# remote_station.net
KiCad netlist of a schematic drawn in EAGLE
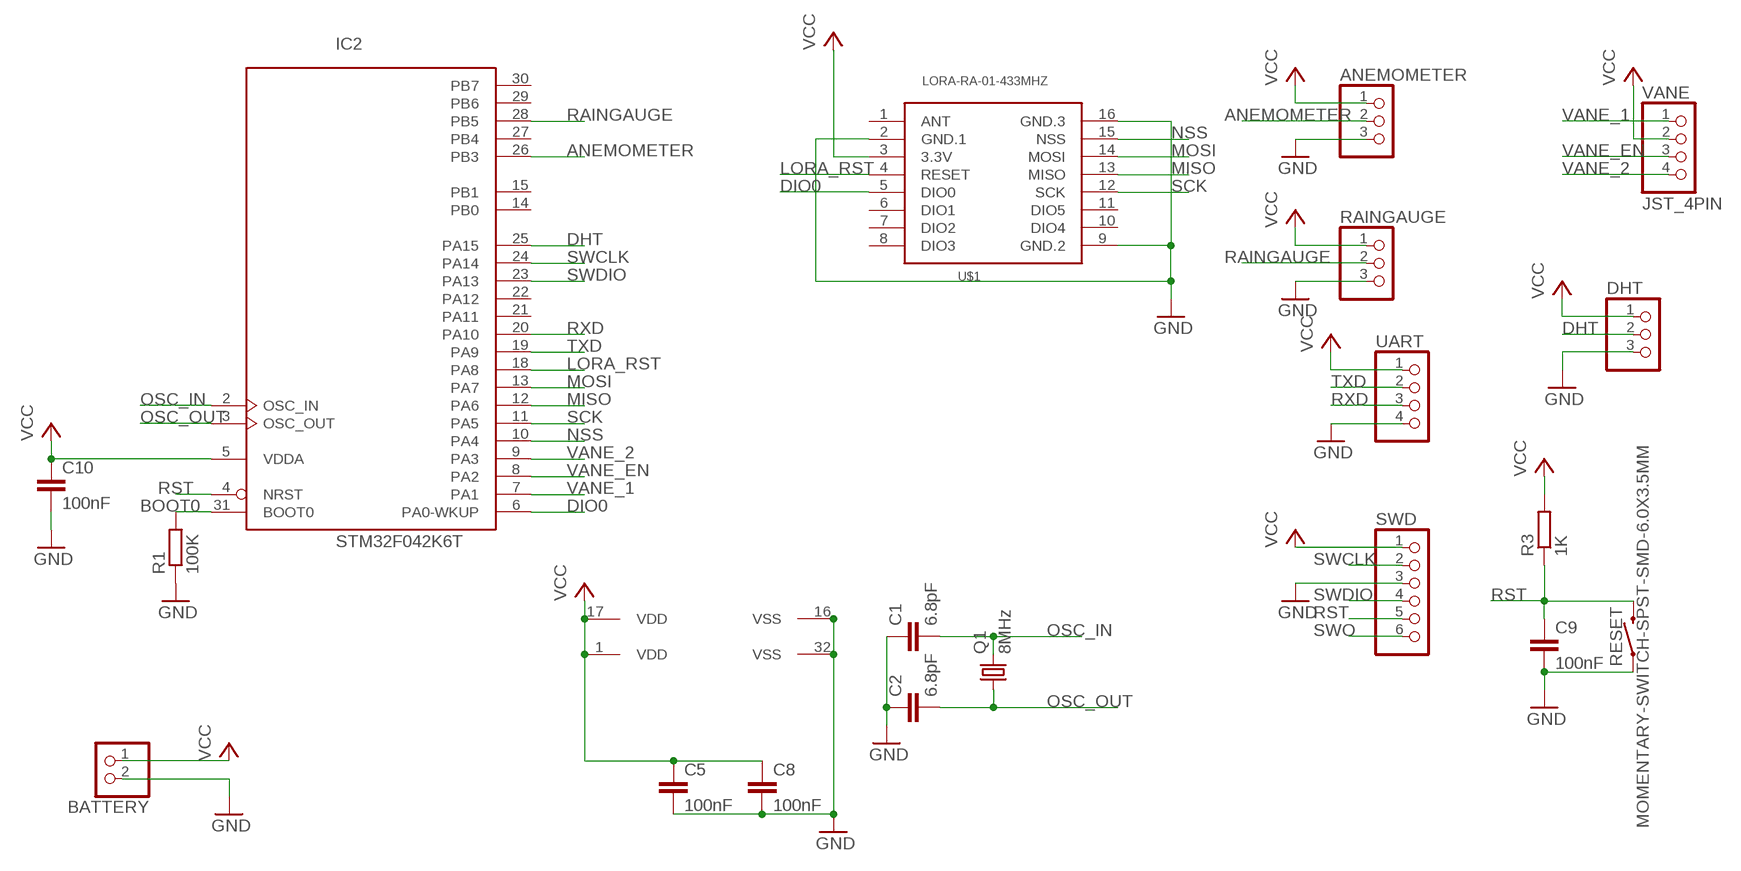
[diagram p0: schematic, sheet 1]

(export (version "E")
  (design (tool "Eeschema 10.0.6"))
  (components
    (comp (ref "ANEMOMETER")
      (value "JST_3PIN")
      (footprint "eagle-import:JSTPH3")
      (libsource (lib "eagle-import") (part "JST_3PIN"))
    )
    (comp (ref "BATTERY")
      (value "JST_2PIN-SMT-RA")
      (footprint "eagle-import:JST-PH-2-SMT-RA")
      (libsource (lib "eagle-import") (part "JST_2PIN-SMT-RA"))
    )
    (comp (ref "C1")
      (value "6.8pF")
      (footprint "eagle-import:C0805K")
      (libsource (lib "eagle-import") (part "C-EUC0805K"))
    )
    (comp (ref "C2")
      (value "6.8pF")
      (footprint "eagle-import:C0805K")
      (libsource (lib "eagle-import") (part "C-EUC0805K"))
    )
    (comp (ref "C5")
      (value "100nF")
      (footprint "eagle-import:C0805K")
      (libsource (lib "eagle-import") (part "C-EUC0805K"))
    )
    (comp (ref "C8")
      (value "100nF")
      (footprint "eagle-import:C0805K")
      (libsource (lib "eagle-import") (part "C-EUC0805K"))
    )
    (comp (ref "C9")
      (value "100nF")
      (footprint "eagle-import:C0805K")
      (libsource (lib "eagle-import") (part "C-EUC0805K"))
    )
    (comp (ref "C10")
      (value "100nF")
      (footprint "eagle-import:C0805K")
      (libsource (lib "eagle-import") (part "C-EUC0805K"))
    )
    (comp (ref "DHT")
      (value "JST_3PIN")
      (footprint "eagle-import:JSTPH3")
      (libsource (lib "eagle-import") (part "JST_3PIN"))
    )
    (comp (ref "IC2")
      (value "STM32F042K6T")
      (footprint "eagle-import:LQFP32")
      (libsource (lib "eagle-import") (part "STM32F042KT6"))
    )
    (comp (ref "Q1")
      (value "8MHz")
      (footprint "eagle-import:HC49UP")
      (libsource (lib "eagle-import") (part "CRYSTALHC49UP"))
    )
    (comp (ref "R1")
      (value "100K")
      (footprint "eagle-import:R0805W")
      (libsource (lib "eagle-import") (part "R-EU_R0805W"))
    )
    (comp (ref "R3")
      (value "1K")
      (footprint "eagle-import:R0805W")
      (libsource (lib "eagle-import") (part "R-EU_R0805W"))
    )
    (comp (ref "RAINGAUGE")
      (value "JST_3PIN")
      (footprint "eagle-import:JSTPH3")
      (libsource (lib "eagle-import") (part "JST_3PIN"))
    )
    (comp (ref "RESET")
      (value "MOMENTARY-SWITCH-SPST-SMD-6.0X3.5MM")
      (footprint "eagle-import:TACTILE_SWITCH_SMD_6.0X3.5MM")
      (libsource (lib "eagle-import") (part "MOMENTARY-SWITCH-SPST-SMD-6.0X3.5MM"))
    )
    (comp (ref "SWD")
      (value "PINHD-1X6")
      (footprint "eagle-import:1X06")
      (libsource (lib "eagle-import") (part "PINHD-1X6"))
    )
    (comp (ref "U$1")
      (value "LORA-RA-01-433MHZ")
      (footprint "eagle-import:LORA-RA1-SMD")
      (libsource (lib "eagle-import") (part "LORA-RA-01-433MHZ"))
    )
    (comp (ref "UART")
      (value "PINHD-1X4")
      (footprint "eagle-import:1X04")
      (libsource (lib "eagle-import") (part "PINHD-1X4"))
    )
    (comp (ref "VANE")
      (value "JST_4PIN")
      (footprint "eagle-import:JST-PH-2-SMT-RA")
      (libsource (lib "eagle-import") (part "JST_4PIN"))
    )
  )
  (nets
    (net (code "1") (name "/ANEMOMETER") (class "Default")
      (node (ref "ANEMOMETER") (pin "2") (pinfunction "2_2") (pintype "passive"))
      (node (ref "IC2") (pin "26") (pinfunction "PB3_26") (pintype "bidirectional"))
    )
    (net (code "2") (name "/BOOT0") (class "Default")
      (node (ref "IC2") (pin "31") (pinfunction "BOOT0_31") (pintype "input"))
      (node (ref "R1") (pin "2") (pinfunction "2_2") (pintype "passive"))
    )
    (net (code "3") (name "/DHT") (class "Default")
      (node (ref "DHT") (pin "2") (pinfunction "2_2") (pintype "passive"))
      (node (ref "IC2") (pin "25") (pinfunction "PA15_25") (pintype "bidirectional"))
    )
    (net (code "4") (name "/DIO0") (class "Default")
      (node (ref "IC2") (pin "6") (pinfunction "PA0-WKUP_6") (pintype "bidirectional"))
      (node (ref "U$1") (pin "5") (pinfunction "DIO0_5") (pintype "bidirectional"))
    )
    (net (code "5") (name "/LORA_RST") (class "Default")
      (node (ref "IC2") (pin "18") (pinfunction "PA8_18") (pintype "bidirectional"))
      (node (ref "U$1") (pin "4") (pinfunction "RESET_4") (pintype "bidirectional"))
    )
    (net (code "6") (name "/MISO") (class "Default")
      (node (ref "IC2") (pin "12") (pinfunction "PA6_12") (pintype "bidirectional"))
      (node (ref "U$1") (pin "13") (pinfunction "MISO_13") (pintype "bidirectional"))
    )
    (net (code "7") (name "/MOSI") (class "Default")
      (node (ref "IC2") (pin "13") (pinfunction "PA7_13") (pintype "bidirectional"))
      (node (ref "U$1") (pin "14") (pinfunction "MOSI_14") (pintype "bidirectional"))
    )
    (net (code "8") (name "/NSS") (class "Default")
      (node (ref "IC2") (pin "10") (pinfunction "PA4_10") (pintype "bidirectional"))
      (node (ref "U$1") (pin "15") (pinfunction "NSS_15") (pintype "bidirectional"))
    )
    (net (code "9") (name "/OSC_IN") (class "Default")
      (node (ref "C1") (pin "2") (pinfunction "2_2") (pintype "passive"))
      (node (ref "IC2") (pin "2") (pinfunction "OSC_IN_2") (pintype "bidirectional"))
      (node (ref "Q1") (pin "2") (pinfunction "2_2") (pintype "passive"))
    )
    (net (code "10") (name "/OSC_OUT") (class "Default")
      (node (ref "C2") (pin "2") (pinfunction "2_2") (pintype "passive"))
      (node (ref "IC2") (pin "3") (pinfunction "OSC_OUT_3") (pintype "bidirectional"))
      (node (ref "Q1") (pin "1") (pinfunction "1_1") (pintype "passive"))
    )
    (net (code "11") (name "/RAINGAUGE") (class "Default")
      (node (ref "IC2") (pin "28") (pinfunction "PB5_28") (pintype "bidirectional"))
      (node (ref "RAINGAUGE") (pin "2") (pinfunction "2_2") (pintype "passive"))
    )
    (net (code "12") (name "/RST") (class "Default")
      (node (ref "C9") (pin "1") (pinfunction "1_1") (pintype "passive"))
      (node (ref "IC2") (pin "4") (pinfunction "NRST_4") (pintype "bidirectional"))
      (node (ref "R3") (pin "1") (pinfunction "1_1") (pintype "passive"))
      (node (ref "RESET") (pin "2") (pinfunction "2_2") (pintype "passive"))
      (node (ref "SWD") (pin "5") (pinfunction "5_5") (pintype "passive"))
    )
    (net (code "13") (name "/RXD") (class "Default")
      (node (ref "IC2") (pin "20") (pinfunction "PA10_20") (pintype "bidirectional"))
      (node (ref "UART") (pin "3") (pinfunction "3_3") (pintype "passive"))
    )
    (net (code "14") (name "/SCK") (class "Default")
      (node (ref "IC2") (pin "11") (pinfunction "PA5_11") (pintype "bidirectional"))
      (node (ref "U$1") (pin "12") (pinfunction "SCK_12") (pintype "bidirectional"))
    )
    (net (code "15") (name "/SWCLK") (class "Default")
      (node (ref "IC2") (pin "24") (pinfunction "PA14_24") (pintype "bidirectional"))
      (node (ref "SWD") (pin "2") (pinfunction "2_2") (pintype "passive"))
    )
    (net (code "16") (name "/SWDIO") (class "Default")
      (node (ref "IC2") (pin "23") (pinfunction "PA13_23") (pintype "bidirectional"))
      (node (ref "SWD") (pin "4") (pinfunction "4_4") (pintype "passive"))
    )
    (net (code "17") (name "/SWO") (class "Default")
      (node (ref "SWD") (pin "6") (pinfunction "6_6") (pintype "passive"))
    )
    (net (code "18") (name "/TXD") (class "Default")
      (node (ref "IC2") (pin "19") (pinfunction "PA9_19") (pintype "bidirectional"))
      (node (ref "UART") (pin "2") (pinfunction "2_2") (pintype "passive"))
    )
    (net (code "19") (name "/VANE_1") (class "Default")
      (node (ref "IC2") (pin "7") (pinfunction "PA1_7") (pintype "bidirectional"))
      (node (ref "VANE") (pin "1") (pinfunction "1_1") (pintype "passive"))
    )
    (net (code "20") (name "/VANE_2") (class "Default")
      (node (ref "IC2") (pin "9") (pinfunction "PA3_9") (pintype "bidirectional"))
      (node (ref "VANE") (pin "4") (pinfunction "4_4") (pintype "passive"))
    )
    (net (code "21") (name "/VANE_EN") (class "Default")
      (node (ref "IC2") (pin "8") (pinfunction "PA2_8") (pintype "bidirectional"))
      (node (ref "VANE") (pin "3") (pinfunction "3_3") (pintype "passive"))
    )
    (net (code "22") (name "GND") (class "Default")
      (node (ref "ANEMOMETER") (pin "3") (pinfunction "3_3") (pintype "passive"))
      (node (ref "BATTERY") (pin "2") (pinfunction "1_2") (pintype "passive"))
      (node (ref "C1") (pin "1") (pinfunction "1_1") (pintype "passive"))
      (node (ref "C10") (pin "2") (pinfunction "2_2") (pintype "passive"))
      (node (ref "C2") (pin "1") (pinfunction "1_1") (pintype "passive"))
      (node (ref "C5") (pin "2") (pinfunction "2_2") (pintype "passive"))
      (node (ref "C8") (pin "2") (pinfunction "2_2") (pintype "passive"))
      (node (ref "C9") (pin "2") (pinfunction "2_2") (pintype "passive"))
      (node (ref "DHT") (pin "3") (pinfunction "3_3") (pintype "passive"))
      (node (ref "IC2") (pin "16") (pinfunction "VSS_16") (pintype "power_in"))
      (node (ref "IC2") (pin "32") (pinfunction "VSS_32") (pintype "power_in"))
      (node (ref "R1") (pin "1") (pinfunction "1_1") (pintype "passive"))
      (node (ref "RAINGAUGE") (pin "3") (pinfunction "3_3") (pintype "passive"))
      (node (ref "RESET") (pin "1") (pinfunction "1_1") (pintype "passive"))
      (node (ref "SWD") (pin "3") (pinfunction "3_3") (pintype "passive"))
      (node (ref "U$1") (pin "16") (pinfunction "GND.3_16") (pintype "power_in"))
      (node (ref "U$1") (pin "2") (pinfunction "GND.1_2") (pintype "power_in"))
      (node (ref "U$1") (pin "9") (pinfunction "GND.2_9") (pintype "power_in"))
      (node (ref "UART") (pin "4") (pinfunction "4_4") (pintype "passive"))
    )
    (net (code "23") (name "VCC") (class "Default")
      (node (ref "ANEMOMETER") (pin "1") (pinfunction "1_1") (pintype "passive"))
      (node (ref "BATTERY") (pin "1") (pinfunction "2_1") (pintype "passive"))
      (node (ref "C10") (pin "1") (pinfunction "1_1") (pintype "passive"))
      (node (ref "C5") (pin "1") (pinfunction "1_1") (pintype "passive"))
      (node (ref "C8") (pin "1") (pinfunction "1_1") (pintype "passive"))
      (node (ref "DHT") (pin "1") (pinfunction "1_1") (pintype "passive"))
      (node (ref "IC2") (pin "1") (pinfunction "VDD_1") (pintype "power_in"))
      (node (ref "IC2") (pin "17") (pinfunction "VDD_17") (pintype "power_in"))
      (node (ref "IC2") (pin "5") (pinfunction "VDDA_5") (pintype "power_in"))
      (node (ref "R3") (pin "2") (pinfunction "2_2") (pintype "passive"))
      (node (ref "RAINGAUGE") (pin "1") (pinfunction "1_1") (pintype "passive"))
      (node (ref "SWD") (pin "1") (pinfunction "1_1") (pintype "passive"))
      (node (ref "U$1") (pin "3") (pinfunction "3.3V_3") (pintype "power_in"))
      (node (ref "UART") (pin "1") (pinfunction "1_1") (pintype "passive"))
      (node (ref "VANE") (pin "2") (pinfunction "2_2") (pintype "passive"))
    )
    (net (code "24") (name "unconnected-(IC2A-PA11-Pad21)") (class "Default")
      (node (ref "IC2") (pin "21") (pinfunction "PA11_21") (pintype "bidirectional"))
    )
    (net (code "25") (name "unconnected-(IC2A-PA12-Pad22)") (class "Default")
      (node (ref "IC2") (pin "22") (pinfunction "PA12_22") (pintype "bidirectional"))
    )
    (net (code "26") (name "unconnected-(IC2A-PB0-Pad14)") (class "Default")
      (node (ref "IC2") (pin "14") (pinfunction "PB0_14") (pintype "bidirectional"))
    )
    (net (code "27") (name "unconnected-(IC2A-PB1-Pad15)") (class "Default")
      (node (ref "IC2") (pin "15") (pinfunction "PB1_15") (pintype "bidirectional"))
    )
    (net (code "28") (name "unconnected-(IC2A-PB4-Pad27)") (class "Default")
      (node (ref "IC2") (pin "27") (pinfunction "PB4_27") (pintype "bidirectional"))
    )
    (net (code "29") (name "unconnected-(IC2A-PB6-Pad29)") (class "Default")
      (node (ref "IC2") (pin "29") (pinfunction "PB6_29") (pintype "bidirectional"))
    )
    (net (code "30") (name "unconnected-(IC2A-PB7-Pad30)") (class "Default")
      (node (ref "IC2") (pin "30") (pinfunction "PB7_30") (pintype "bidirectional"))
    )
    (net (code "31") (name "unconnected-(U$1-ANT-Pad1)") (class "Default")
      (node (ref "U$1") (pin "1") (pinfunction "ANT_1") (pintype "bidirectional"))
    )
    (net (code "32") (name "unconnected-(U$1-DIO1-Pad6)") (class "Default")
      (node (ref "U$1") (pin "6") (pinfunction "DIO1_6") (pintype "bidirectional"))
    )
    (net (code "33") (name "unconnected-(U$1-DIO2-Pad7)") (class "Default")
      (node (ref "U$1") (pin "7") (pinfunction "DIO2_7") (pintype "bidirectional"))
    )
    (net (code "34") (name "unconnected-(U$1-DIO3-Pad8)") (class "Default")
      (node (ref "U$1") (pin "8") (pinfunction "DIO3_8") (pintype "bidirectional"))
    )
    (net (code "35") (name "unconnected-(U$1-DIO4-Pad10)") (class "Default")
      (node (ref "U$1") (pin "10") (pinfunction "DIO4_10") (pintype "bidirectional"))
    )
    (net (code "36") (name "unconnected-(U$1-DIO5-Pad11)") (class "Default")
      (node (ref "U$1") (pin "11") (pinfunction "DIO5_11") (pintype "bidirectional"))
    )
  )
)
